# Mezclador1.net
KiCad netlist of a schematic drawn in Altium Designer
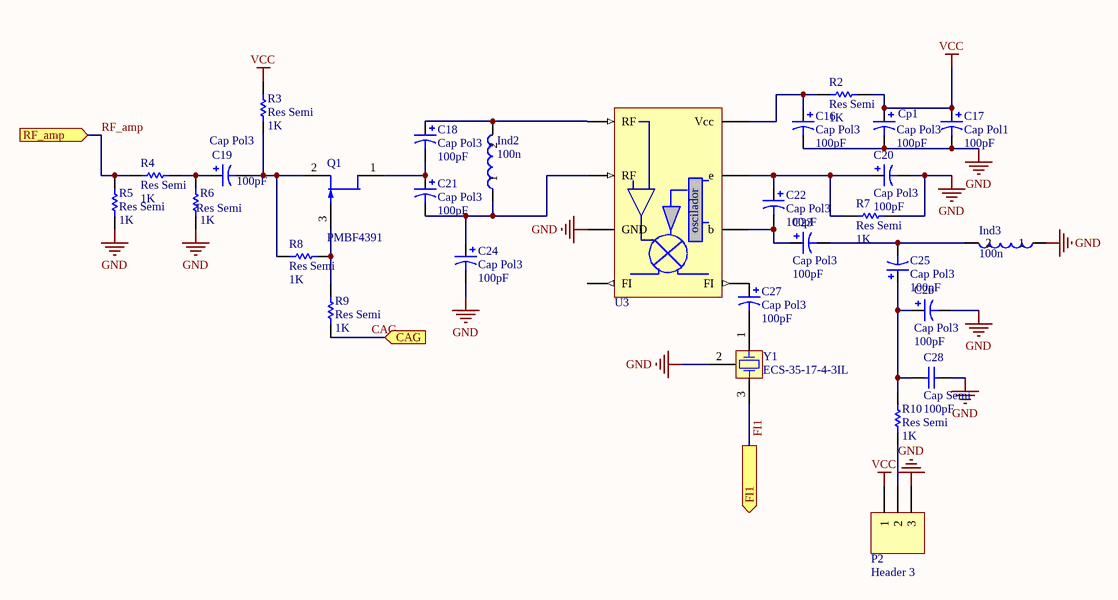
[diagram p0: Mezclador1.SchDoc]

(export (version "E")
  (design (tool "Eeschema 10.0.6"))
  (components
    (comp (ref "C16")
      (value "Cap Pol3")
      (footprint "C0805")
      (description "Polarized Capacitor (Surface Mount)")
      (fields (field (name "ALTIUM_VALUE") "100pF") (field (name "PUBLISHER") "Altium Limited"))
      (libsource (lib "Miscellaneous Devices") (part "Cap Pol3"))
    )
    (comp (ref "C17")
      (value "Cap Pol1")
      (footprint "B")
      (description "Polarized Capacitor (Radial)")
      (fields (field (name "ALTIUM_VALUE") "100pF") (field (name "PUBLISHER") "Altium Limited"))
      (libsource (lib "Miscellaneous Devices") (part "Cap Pol1"))
    )
    (comp (ref "C18")
      (value "Cap Pol3")
      (footprint "C0805")
      (description "Polarized Capacitor (Surface Mount)")
      (fields (field (name "ALTIUM_VALUE") "100pF") (field (name "PUBLISHER") "Altium Limited"))
      (libsource (lib "Miscellaneous Devices") (part "Cap Pol3"))
    )
    (comp (ref "C19")
      (value "Cap Pol3")
      (footprint "C0805")
      (description "Polarized Capacitor (Surface Mount)")
      (fields (field (name "ALTIUM_VALUE") "100pF") (field (name "PUBLISHER") "Altium Limited"))
      (libsource (lib "Miscellaneous Devices") (part "Cap Pol3"))
    )
    (comp (ref "C20")
      (value "Cap Pol3")
      (footprint "C0805")
      (description "Polarized Capacitor (Surface Mount)")
      (fields (field (name "ALTIUM_VALUE") "100pF") (field (name "PUBLISHER") "Altium Limited"))
      (libsource (lib "Miscellaneous Devices") (part "Cap Pol3"))
    )
    (comp (ref "C21")
      (value "Cap Pol3")
      (footprint "C0805")
      (description "Polarized Capacitor (Surface Mount)")
      (fields (field (name "ALTIUM_VALUE") "100pF") (field (name "PUBLISHER") "Altium Limited"))
      (libsource (lib "Miscellaneous Devices") (part "Cap Pol3"))
    )
    (comp (ref "C22")
      (value "Cap Pol3")
      (footprint "C0805")
      (description "Polarized Capacitor (Surface Mount)")
      (fields (field (name "ALTIUM_VALUE") "100pF") (field (name "PUBLISHER") "Altium Limited"))
      (libsource (lib "Miscellaneous Devices") (part "Cap Pol3"))
    )
    (comp (ref "C23")
      (value "Cap Pol3")
      (footprint "C0805")
      (description "Polarized Capacitor (Surface Mount)")
      (fields (field (name "ALTIUM_VALUE") "100pF") (field (name "PUBLISHER") "Altium Limited"))
      (libsource (lib "Miscellaneous Devices") (part "Cap Pol3"))
    )
    (comp (ref "C24")
      (value "Cap Pol3")
      (footprint "C0805")
      (description "Polarized Capacitor (Surface Mount)")
      (fields (field (name "ALTIUM_VALUE") "100pF") (field (name "PUBLISHER") "Altium Limited"))
      (libsource (lib "Miscellaneous Devices") (part "Cap Pol3"))
    )
    (comp (ref "C25")
      (value "Cap Pol3")
      (footprint "C0805")
      (description "Polarized Capacitor (Surface Mount)")
      (fields (field (name "ALTIUM_VALUE") "100pF") (field (name "PUBLISHER") "Altium Limited"))
      (libsource (lib "Miscellaneous Devices") (part "Cap Pol3"))
    )
    (comp (ref "C26")
      (value "Cap Pol3")
      (footprint "C0805")
      (description "Polarized Capacitor (Surface Mount)")
      (fields (field (name "ALTIUM_VALUE") "100pF") (field (name "PUBLISHER") "Altium Limited"))
      (libsource (lib "Miscellaneous Devices") (part "Cap Pol3"))
    )
    (comp (ref "C27")
      (value "Cap Pol3")
      (footprint "C0805")
      (description "Polarized Capacitor (Surface Mount)")
      (fields (field (name "ALTIUM_VALUE") "100pF") (field (name "PUBLISHER") "Altium Limited"))
      (libsource (lib "Miscellaneous Devices") (part "Cap Pol3"))
    )
    (comp (ref "C28")
      (value "Cap Semi")
      (footprint "C1206")
      (description "Capacitor (Semiconductor SIM Model)")
      (fields (field (name "ALTIUM_VALUE") "100pF") (field (name "PUBLISHER") "Altium Limited"))
      (libsource (lib "Miscellaneous Devices") (part "Cap Semi"))
    )
    (comp (ref "Cp1")
      (value "Cap Pol3")
      (footprint "C0805")
      (description "Polarized Capacitor (Surface Mount)")
      (fields (field (name "ALTIUM_VALUE") "100pF") (field (name "PUBLISHER") "Altium Limited"))
      (libsource (lib "Miscellaneous Devices") (part "Cap Pol3"))
    )
    (comp (ref "Ind2")
      (value "Ind2")
      (footprint "Ind_5mm")
      (fields (field (name "VALOR") "100n"))
      (libsource (lib "epf") (part "Ind2"))
    )
    (comp (ref "Ind3")
      (value "Ind2")
      (footprint "Ind_4mm")
      (fields (field (name "VALOR") "100n"))
      (libsource (lib "epf") (part "Ind2"))
    )
    (comp (ref "P2")
      (value "Header 3")
      (footprint "HDR1X3")
      (description "Header, 3-Pin")
      (fields (field (name "PUBLISHER") "Altium Limited"))
      (libsource (lib "Miscellaneous Connectors") (part "Header 3"))
    )
    (comp (ref "Q1")
      (value "PMBF4391")
      (footprint "SOT23_N")
      (description "N-channel Silicon Junction Field-effect Transistor")
      (fields (field (name "PUBLISHER") "Altium Limited"))
      (libsource (lib "Philips Discrete JFET") (part "PMBF4391"))
    )
    (comp (ref "R2")
      (value "Res Semi")
      (footprint "2012[0805]")
      (description "Semiconductor Resistor")
      (fields (field (name "ALTIUM_VALUE") "1K") (field (name "PUBLISHER") "Altium Limited"))
      (libsource (lib "Miscellaneous Devices") (part "Res Semi"))
    )
    (comp (ref "R3")
      (value "Res Semi")
      (footprint "2012[0805]")
      (description "Semiconductor Resistor")
      (fields (field (name "ALTIUM_VALUE") "1K") (field (name "PUBLISHER") "Altium Limited"))
      (libsource (lib "Miscellaneous Devices") (part "Res Semi"))
    )
    (comp (ref "R4")
      (value "Res Semi")
      (footprint "2012[0805]")
      (description "Semiconductor Resistor")
      (fields (field (name "ALTIUM_VALUE") "1K") (field (name "PUBLISHER") "Altium Limited"))
      (libsource (lib "Miscellaneous Devices") (part "Res Semi"))
    )
    (comp (ref "R5")
      (value "Res Semi")
      (footprint "2012[0805]")
      (description "Semiconductor Resistor")
      (fields (field (name "ALTIUM_VALUE") "1K") (field (name "PUBLISHER") "Altium Limited"))
      (libsource (lib "Miscellaneous Devices") (part "Res Semi"))
    )
    (comp (ref "R6")
      (value "Res Semi")
      (footprint "2012[0805]")
      (description "Semiconductor Resistor")
      (fields (field (name "ALTIUM_VALUE") "1K") (field (name "PUBLISHER") "Altium Limited"))
      (libsource (lib "Miscellaneous Devices") (part "Res Semi"))
    )
    (comp (ref "R7")
      (value "Res Semi")
      (footprint "2012[0805]")
      (description "Semiconductor Resistor")
      (fields (field (name "ALTIUM_VALUE") "1K") (field (name "PUBLISHER") "Altium Limited"))
      (libsource (lib "Miscellaneous Devices") (part "Res Semi"))
    )
    (comp (ref "R8")
      (value "Res Semi")
      (footprint "2012[0805]")
      (description "Semiconductor Resistor")
      (fields (field (name "ALTIUM_VALUE") "1K") (field (name "PUBLISHER") "Altium Limited"))
      (libsource (lib "Miscellaneous Devices") (part "Res Semi"))
    )
    (comp (ref "R9")
      (value "Res Semi")
      (footprint "2012[0805]")
      (description "Semiconductor Resistor")
      (fields (field (name "ALTIUM_VALUE") "1K") (field (name "PUBLISHER") "Altium Limited"))
      (libsource (lib "Miscellaneous Devices") (part "Res Semi"))
    )
    (comp (ref "R10")
      (value "Res Semi")
      (footprint "2012[0805]")
      (description "Semiconductor Resistor")
      (fields (field (name "ALTIUM_VALUE") "1K") (field (name "PUBLISHER") "Altium Limited"))
      (libsource (lib "Miscellaneous Devices") (part "Res Semi"))
    )
    (comp (ref "U3")
      (value "SA602")
      (footprint "SA602")
      (description "Mezclador 500MHz")
      (libsource (lib "epf") (part "SA602A"))
    )
    (comp (ref "Y1")
      (value "ECS-35-17-4-3IL")
      (footprint "HC-49US")
      (description "Crystal Oscillator, 3rd In-Line Lead Version")
      (fields (field (name "PUBLISHER") "Altium Limited"))
      (libsource (lib "ECS Crystal Oscillator") (part "ECS-35-17-4-3IL"))
    )
  )
  (nets
    (net (code "1") (name "/CAG") (class "Default")
      (node (ref "R9") (pin "2") (pinfunction "2_2") (pintype "passive"))
    )
    (net (code "2") (name "/FI1") (class "Default")
      (node (ref "Y1") (pin "3") (pinfunction "OSC2_3") (pintype "passive"))
    )
    (net (code "3") (name "/RF_amp") (class "Default")
      (node (ref "R4") (pin "1") (pinfunction "1_1") (pintype "passive"))
      (node (ref "R5") (pin "2") (pinfunction "2_2") (pintype "passive"))
    )
    (net (code "4") (name "GND") (class "Default")
      (node (ref "C16") (pin "2") (pinfunction "2_2") (pintype "passive"))
      (node (ref "C17") (pin "2") (pinfunction "2_2") (pintype "passive"))
      (node (ref "C20") (pin "2") (pinfunction "2_2") (pintype "passive"))
      (node (ref "C24") (pin "2") (pinfunction "2_2") (pintype "passive"))
      (node (ref "C26") (pin "2") (pinfunction "2_2") (pintype "passive"))
      (node (ref "C28") (pin "2") (pinfunction "2_2") (pintype "passive"))
      (node (ref "Cp1") (pin "2") (pinfunction "2_2") (pintype "passive"))
      (node (ref "Ind3") (pin "1") (pinfunction "1_1") (pintype "passive"))
      (node (ref "P2") (pin "3") (pinfunction "3_3") (pintype "passive"))
      (node (ref "R5") (pin "1") (pinfunction "1_1") (pintype "passive"))
      (node (ref "R6") (pin "1") (pinfunction "1_1") (pintype "passive"))
      (node (ref "R7") (pin "1") (pinfunction "1_1") (pintype "passive"))
      (node (ref "U3") (pin "3") (pinfunction "GND_3") (pintype "passive"))
      (node (ref "Y1") (pin "2") (pinfunction "COM_2") (pintype "passive"))
    )
    (net (code "5") (name "Net-(C18-Pad1)") (class "Default")
      (node (ref "C18") (pin "1") (pinfunction "1_1") (pintype "passive"))
      (node (ref "Ind2") (pin "2") (pinfunction "2_2") (pintype "passive"))
      (node (ref "U3") (pin "1") (pinfunction "RF_1") (pintype "input"))
    )
    (net (code "6") (name "Net-(C19-Pad1)") (class "Default")
      (node (ref "C19") (pin "1") (pinfunction "1_1") (pintype "passive"))
      (node (ref "R4") (pin "2") (pinfunction "2_2") (pintype "passive"))
      (node (ref "R6") (pin "2") (pinfunction "2_2") (pintype "passive"))
    )
    (net (code "7") (name "Net-(C21-Pad2)") (class "Default")
      (node (ref "C21") (pin "2") (pinfunction "2_2") (pintype "passive"))
      (node (ref "C24") (pin "1") (pinfunction "1_1") (pintype "passive"))
      (node (ref "Ind2") (pin "1") (pinfunction "1_1") (pintype "passive"))
      (node (ref "U3") (pin "2") (pinfunction "RF_2") (pintype "input"))
    )
    (net (code "8") (name "Net-(C23-Pad2)") (class "Default")
      (node (ref "C23") (pin "2") (pinfunction "2_2") (pintype "passive"))
      (node (ref "C25") (pin "2") (pinfunction "2_2") (pintype "passive"))
      (node (ref "Ind3") (pin "2") (pinfunction "2_2") (pintype "passive"))
    )
    (net (code "9") (name "Net-(C25-Pad1)") (class "Default")
      (node (ref "C25") (pin "1") (pinfunction "1_1") (pintype "passive"))
      (node (ref "C26") (pin "1") (pinfunction "1_1") (pintype "passive"))
      (node (ref "C28") (pin "1") (pinfunction "1_1") (pintype "passive"))
      (node (ref "R10") (pin "2") (pinfunction "2_2") (pintype "passive"))
    )
    (net (code "10") (name "Net-(C27-Pad1)") (class "Default")
      (node (ref "C27") (pin "1") (pinfunction "1_1") (pintype "passive"))
      (node (ref "U3") (pin "5") (pinfunction "FI_5") (pintype "output"))
    )
    (net (code "11") (name "Net-(P2-Pad2)") (class "Default")
      (node (ref "P2") (pin "2") (pinfunction "2_2") (pintype "passive"))
      (node (ref "R10") (pin "1") (pinfunction "1_1") (pintype "passive"))
    )
    (net (code "12") (name "Net-(Q1-D)") (class "Default")
      (node (ref "C18") (pin "2") (pinfunction "2_2") (pintype "passive"))
      (node (ref "C21") (pin "1") (pinfunction "1_1") (pintype "passive"))
      (node (ref "Q1") (pin "1") (pinfunction "D_1") (pintype "passive"))
    )
    (net (code "13") (name "Net-(Q1-G)") (class "Default")
      (node (ref "Q1") (pin "3") (pinfunction "G_3") (pintype "passive"))
      (node (ref "R8") (pin "2") (pinfunction "2_2") (pintype "passive"))
      (node (ref "R9") (pin "1") (pinfunction "1_1") (pintype "passive"))
    )
    (net (code "14") (name "Net-(Q1-S)") (class "Default")
      (node (ref "C19") (pin "2") (pinfunction "2_2") (pintype "passive"))
      (node (ref "Q1") (pin "2") (pinfunction "S_2") (pintype "passive"))
      (node (ref "R3") (pin "1") (pinfunction "1_1") (pintype "passive"))
      (node (ref "R8") (pin "1") (pinfunction "1_1") (pintype "passive"))
    )
    (net (code "15") (name "Net-(U3-Vcc)") (class "Default")
      (node (ref "C16") (pin "1") (pinfunction "1_1") (pintype "passive"))
      (node (ref "R2") (pin "1") (pinfunction "1_1") (pintype "passive"))
      (node (ref "U3") (pin "8") (pinfunction "Vcc_8") (pintype "passive"))
    )
    (net (code "16") (name "Net-(U3-b)") (class "Default")
      (node (ref "C22") (pin "2") (pinfunction "2_2") (pintype "passive"))
      (node (ref "C23") (pin "1") (pinfunction "1_1") (pintype "passive"))
      (node (ref "U3") (pin "6") (pinfunction "b_6") (pintype "passive"))
    )
    (net (code "17") (name "Net-(U3-e)") (class "Default")
      (node (ref "C20") (pin "1") (pinfunction "1_1") (pintype "passive"))
      (node (ref "C22") (pin "1") (pinfunction "1_1") (pintype "passive"))
      (node (ref "R7") (pin "2") (pinfunction "2_2") (pintype "passive"))
      (node (ref "U3") (pin "7") (pinfunction "e_7") (pintype "passive"))
    )
    (net (code "18") (name "Net-(Y1-OSC1)") (class "Default")
      (node (ref "C27") (pin "2") (pinfunction "2_2") (pintype "passive"))
      (node (ref "Y1") (pin "1") (pinfunction "OSC1_1") (pintype "passive"))
    )
    (net (code "19") (name "VCC") (class "Default")
      (node (ref "C17") (pin "1") (pinfunction "1_1") (pintype "passive"))
      (node (ref "Cp1") (pin "1") (pinfunction "1_1") (pintype "passive"))
      (node (ref "P2") (pin "1") (pinfunction "1_1") (pintype "passive"))
      (node (ref "R2") (pin "2") (pinfunction "2_2") (pintype "passive"))
      (node (ref "R3") (pin "2") (pinfunction "2_2") (pintype "passive"))
    )
    (net (code "20") (name "unconnected-(U3-FI-Pad4)") (class "Default")
      (node (ref "U3") (pin "4") (pinfunction "FI_4") (pintype "output"))
    )
  )
)
